# LLC.net
KiCad netlist of a schematic drawn in EAGLE
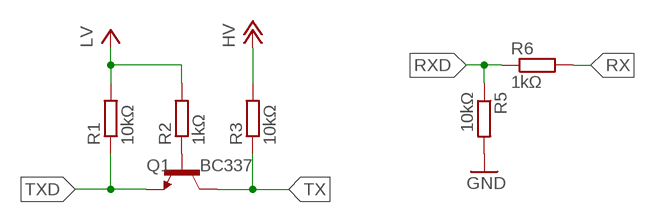
[diagram p0: schematic, sheet 1]

(export (version "E")
  (design (tool "Eeschema 10.0.6"))
  (components
    (comp (ref "Q1")
      (value "BC337")
      (footprint "eagle-import:TO92-EBC")
      (libsource (lib "eagle-import") (part "BC337"))
    )
    (comp (ref "R1")
      (value "10kΩ")
      (footprint "eagle-import:RCL_0207_10")
      (libsource (lib "eagle-import") (part "RCL_R-EU_0207/10"))
    )
    (comp (ref "R2")
      (value "1kΩ")
      (footprint "eagle-import:RCL_0207_10")
      (libsource (lib "eagle-import") (part "RCL_R-EU_0207/10"))
    )
    (comp (ref "R3")
      (value "10kΩ")
      (footprint "eagle-import:RCL_0207_10")
      (libsource (lib "eagle-import") (part "RCL_R-EU_0207/10"))
    )
    (comp (ref "R5")
      (value "10kΩ")
      (footprint "eagle-import:RCL_0207_10")
      (libsource (lib "eagle-import") (part "RCL_R-EU_0207/10"))
    )
    (comp (ref "R6")
      (value "1kΩ")
      (footprint "eagle-import:RCL_0207_10")
      (libsource (lib "eagle-import") (part "RCL_R-EU_0207/10"))
    )
  )
  (nets
    (net (code "1") (name "GND") (class "Default")
      (node (ref "R5") (pin "2") (pinfunction "2_2") (pintype "passive"))
    )
    (net (code "2") (name "HV") (class "Default")
      (node (ref "R3") (pin "2") (pinfunction "2_2") (pintype "passive"))
    )
    (net (code "3") (name "LV") (class "Default")
      (node (ref "R1") (pin "2") (pinfunction "2_2") (pintype "passive"))
      (node (ref "R2") (pin "2") (pinfunction "2_2") (pintype "passive"))
    )
    (net (code "4") (name "Net-(Q1-PadB)") (class "Default")
      (node (ref "Q1") (pin "B") (pinfunction "B_B") (pintype "passive"))
      (node (ref "R2") (pin "1") (pinfunction "1_1") (pintype "passive"))
    )
    (net (code "5") (name "RX") (class "Default")
      (node (ref "R6") (pin "2") (pinfunction "2_2") (pintype "passive"))
    )
    (net (code "6") (name "RXD") (class "Default")
      (node (ref "R5") (pin "1") (pinfunction "1_1") (pintype "passive"))
      (node (ref "R6") (pin "1") (pinfunction "1_1") (pintype "passive"))
    )
    (net (code "7") (name "TX") (class "Default")
      (node (ref "Q1") (pin "C") (pinfunction "C_C") (pintype "passive"))
      (node (ref "R3") (pin "1") (pinfunction "1_1") (pintype "passive"))
    )
    (net (code "8") (name "TXD") (class "Default")
      (node (ref "Q1") (pin "E") (pinfunction "E_E") (pintype "passive"))
      (node (ref "R1") (pin "1") (pinfunction "1_1") (pintype "passive"))
    )
  )
)
